# 1-Schematic_Race_project_transmitter.net
KiCad netlist of a schematic drawn in EasyEDA
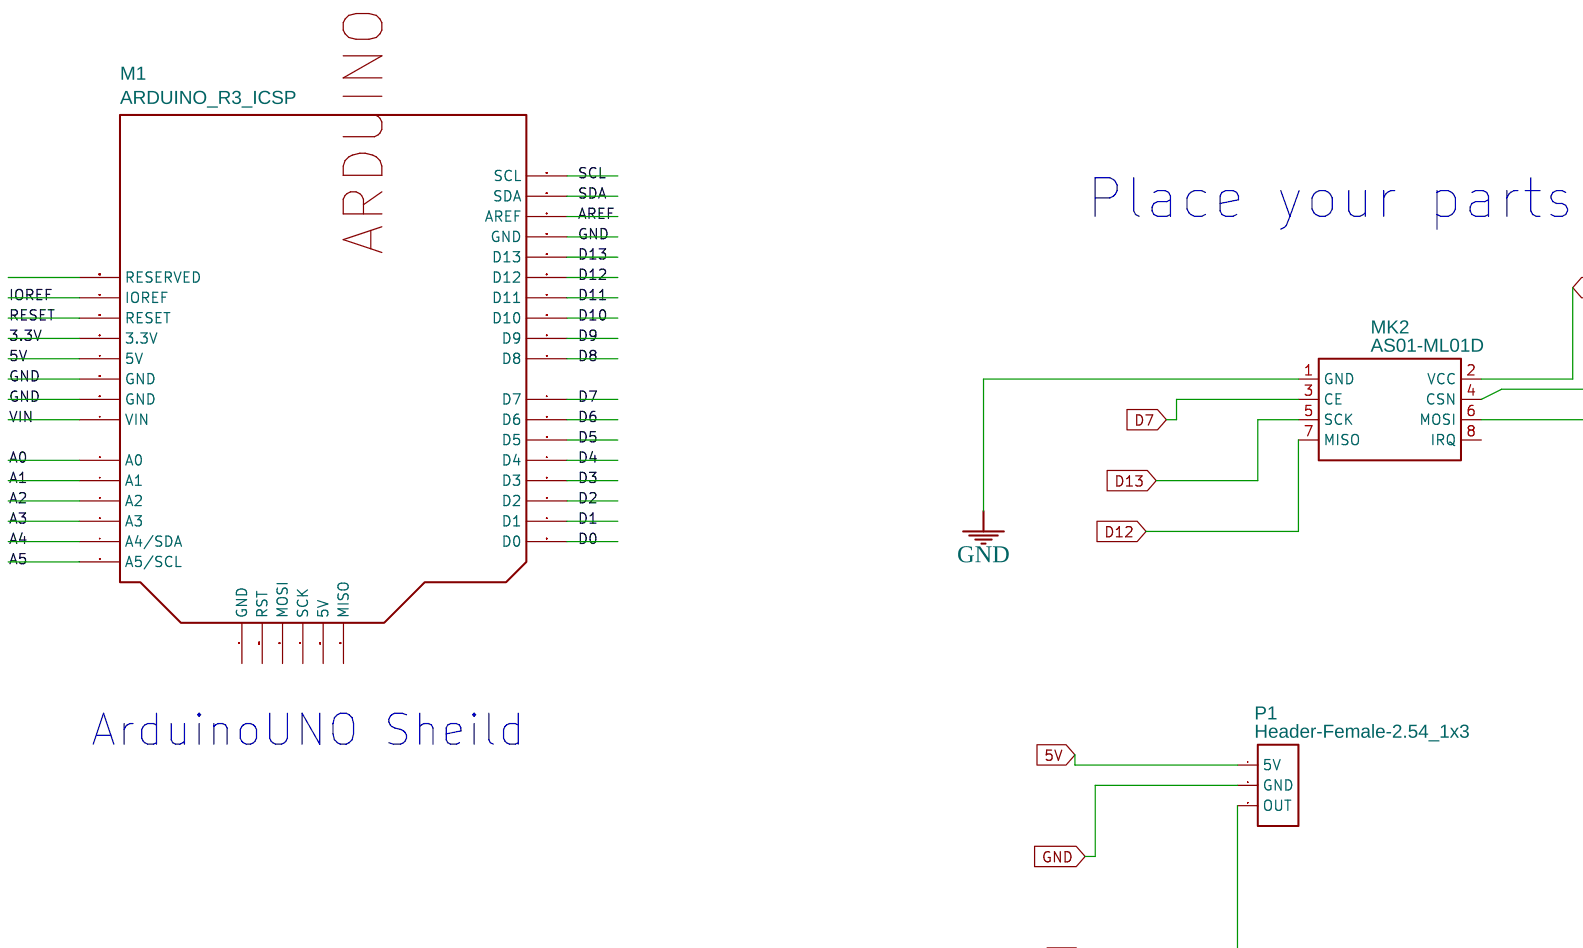
[diagram p0: schematic sheet]

(export (version "E")
  (design (tool "Eeschema 10.0.6"))
  (components
    (comp (ref "M1")
      (value "ARDUINO_R3_ICSP")
      (fields (field (name "BOM_Manufacturer Part") "?"))
      (libsource (lib "") (part "Unknown_20_65"))
    )
    (comp (ref "MK2")
      (value "AS01-ML01D")
      (fields (field (name "BOM_Supplier Part") "C84803"))
      (libsource (lib "") (part "Unknown_645_210"))
    )
    (comp (ref "P1")
      (value "Header-Female-2.54_1x3")
      (fields (field (name "BOM_Supplier Part") "C146243"))
      (libsource (lib "") (part "Unknown_585_395"))
    )
  )
  (nets
    (net (code "1") (name "/A1") (class "Default")
      (node (ref "M1") (pin "A1") (pinfunction "A1_A1") (pintype "unspecified"))
    )
    (net (code "2") (name "/A2") (class "Default")
      (node (ref "M1") (pin "A2") (pinfunction "A2_A2") (pintype "unspecified"))
    )
    (net (code "3") (name "/A3") (class "Default")
      (node (ref "M1") (pin "A3") (pinfunction "A3_A3") (pintype "unspecified"))
    )
    (net (code "4") (name "/A4") (class "Default")
      (node (ref "M1") (pin "A4") (pinfunction "A4/SDA_A4") (pintype "unspecified"))
    )
    (net (code "5") (name "/A5") (class "Default")
      (node (ref "M1") (pin "A5") (pinfunction "A5/SCL_A5") (pintype "unspecified"))
    )
    (net (code "6") (name "/AREF") (class "Default")
      (node (ref "M1") (pin "AREF") (pinfunction "AREF_AREF") (pintype "unspecified"))
    )
    (net (code "7") (name "/D0") (class "Default")
      (node (ref "M1") (pin "D0") (pinfunction "D0_D0") (pintype "unspecified"))
    )
    (net (code "8") (name "/D1") (class "Default")
      (node (ref "M1") (pin "D1") (pinfunction "D1_D1") (pintype "unspecified"))
    )
    (net (code "9") (name "/D2") (class "Default")
      (node (ref "M1") (pin "D2") (pinfunction "D2_D2") (pintype "unspecified"))
    )
    (net (code "10") (name "/D3") (class "Default")
      (node (ref "M1") (pin "D3") (pinfunction "D3_D3") (pintype "unspecified"))
    )
    (net (code "11") (name "/D4") (class "Default")
      (node (ref "M1") (pin "D4") (pinfunction "D4_D4") (pintype "unspecified"))
    )
    (net (code "12") (name "/D5") (class "Default")
      (node (ref "M1") (pin "D5") (pinfunction "D5_D5") (pintype "unspecified"))
    )
    (net (code "13") (name "/D6") (class "Default")
      (node (ref "M1") (pin "D6") (pinfunction "D6_D6") (pintype "unspecified"))
    )
    (net (code "14") (name "/D9") (class "Default")
      (node (ref "M1") (pin "D9") (pinfunction "D9_D9") (pintype "unspecified"))
    )
    (net (code "15") (name "/D10") (class "Default")
      (node (ref "M1") (pin "D10") (pinfunction "D10_D10") (pintype "unspecified"))
    )
    (net (code "16") (name "/IOREF") (class "Default")
      (node (ref "M1") (pin "IOREF") (pinfunction "IOREF_IOREF") (pintype "output"))
    )
    (net (code "17") (name "/RESET") (class "Default")
      (node (ref "M1") (pin "RESET") (pinfunction "RESET_RESET") (pintype "unspecified"))
    )
    (net (code "18") (name "/SCL") (class "Default")
      (node (ref "M1") (pin "SCL") (pinfunction "SCL_SCL") (pintype "unspecified"))
    )
    (net (code "19") (name "/SDA") (class "Default")
      (node (ref "M1") (pin "SDA") (pinfunction "SDA_SDA") (pintype "unspecified"))
    )
    (net (code "20") (name "/VIN") (class "Default")
      (node (ref "M1") (pin "VIN") (pinfunction "VIN_VIN") (pintype "passive"))
    )
    (net (code "21") (name "3.3V") (class "Default")
      (node (ref "M1") (pin "3.3V") (pinfunction "3.3V_3.3V") (pintype "passive"))
      (node (ref "MK2") (pin "2") (pinfunction "VCC_2") (pintype "unspecified"))
    )
    (net (code "22") (name "5V") (class "Default")
      (node (ref "M1") (pin "5V") (pinfunction "5V_5V") (pintype "passive"))
      (node (ref "P1") (pin "1") (pinfunction "5V_1") (pintype "input"))
    )
    (net (code "23") (name "A0") (class "Default")
      (node (ref "M1") (pin "A0") (pinfunction "A0_A0") (pintype "unspecified"))
      (node (ref "P1") (pin "3") (pinfunction "OUT_3") (pintype "input"))
    )
    (net (code "24") (name "D7") (class "Default")
      (node (ref "M1") (pin "D7") (pinfunction "D7_D7") (pintype "unspecified"))
      (node (ref "MK2") (pin "3") (pinfunction "CE_3") (pintype "unspecified"))
    )
    (net (code "25") (name "D8") (class "Default")
      (node (ref "M1") (pin "D8") (pinfunction "D8_D8") (pintype "unspecified"))
      (node (ref "MK2") (pin "4") (pinfunction "CSN_4") (pintype "unspecified"))
    )
    (net (code "26") (name "D11") (class "Default")
      (node (ref "M1") (pin "D11") (pinfunction "D11_D11") (pintype "unspecified"))
      (node (ref "MK2") (pin "6") (pinfunction "MOSI_6") (pintype "unspecified"))
    )
    (net (code "27") (name "D12") (class "Default")
      (node (ref "M1") (pin "D12") (pinfunction "D12_D12") (pintype "unspecified"))
      (node (ref "MK2") (pin "7") (pinfunction "MISO_7") (pintype "unspecified"))
    )
    (net (code "28") (name "D13") (class "Default")
      (node (ref "M1") (pin "D13") (pinfunction "D13_D13") (pintype "unspecified"))
      (node (ref "MK2") (pin "5") (pinfunction "SCK_5") (pintype "unspecified"))
    )
    (net (code "29") (name "GND") (class "Default")
      (node (ref "M1") (pin "GND") (pinfunction "GND_GND") (pintype "passive"))
      (node (ref "MK2") (pin "1") (pinfunction "GND_1") (pintype "unspecified"))
      (node (ref "P1") (pin "2") (pinfunction "GND_2") (pintype "input"))
    )
    (net (code "30") (name "unconnected-(M1-5V-Pad5V_ICSP)") (class "Default")
      (node (ref "M1") (pin "5V_ICSP") (pinfunction "5V_5V_ICSP") (pintype "unspecified"))
    )
    (net (code "31") (name "unconnected-(M1-PadGND)") (class "Default")
      (node (ref "M1") (pin "GND") (pinfunction "GND_GND") (pintype "unspecified"))
    )
    (net (code "32") (name "unconnected-(M1-PadMISO)") (class "Default")
      (node (ref "M1") (pin "MISO") (pinfunction "MISO_MISO") (pintype "unspecified"))
    )
    (net (code "33") (name "unconnected-(M1-PadMOSI)") (class "Default")
      (node (ref "M1") (pin "MOSI") (pinfunction "MOSI_MOSI") (pintype "unspecified"))
    )
    (net (code "34") (name "unconnected-(M1-PadRESERVED)") (class "Default")
      (node (ref "M1") (pin "RESERVED") (pinfunction "RESERVED_RESERVED") (pintype "unspecified"))
    )
    (net (code "35") (name "unconnected-(M1-PadSCK)") (class "Default")
      (node (ref "M1") (pin "SCK") (pinfunction "SCK_SCK") (pintype "unspecified"))
    )
    (net (code "36") (name "unconnected-(M1-RST-PadRESET_ICSP)") (class "Default")
      (node (ref "M1") (pin "RESET_ICSP") (pinfunction "RST_RESET_ICSP") (pintype "unspecified"))
    )
    (net (code "37") (name "unconnected-(MK2-IRQ-Pad8)") (class "Default")
      (node (ref "MK2") (pin "8") (pinfunction "IRQ_8") (pintype "unspecified"))
    )
  )
)
